# sch.net
KiCad netlist of a schematic drawn in EasyEDA
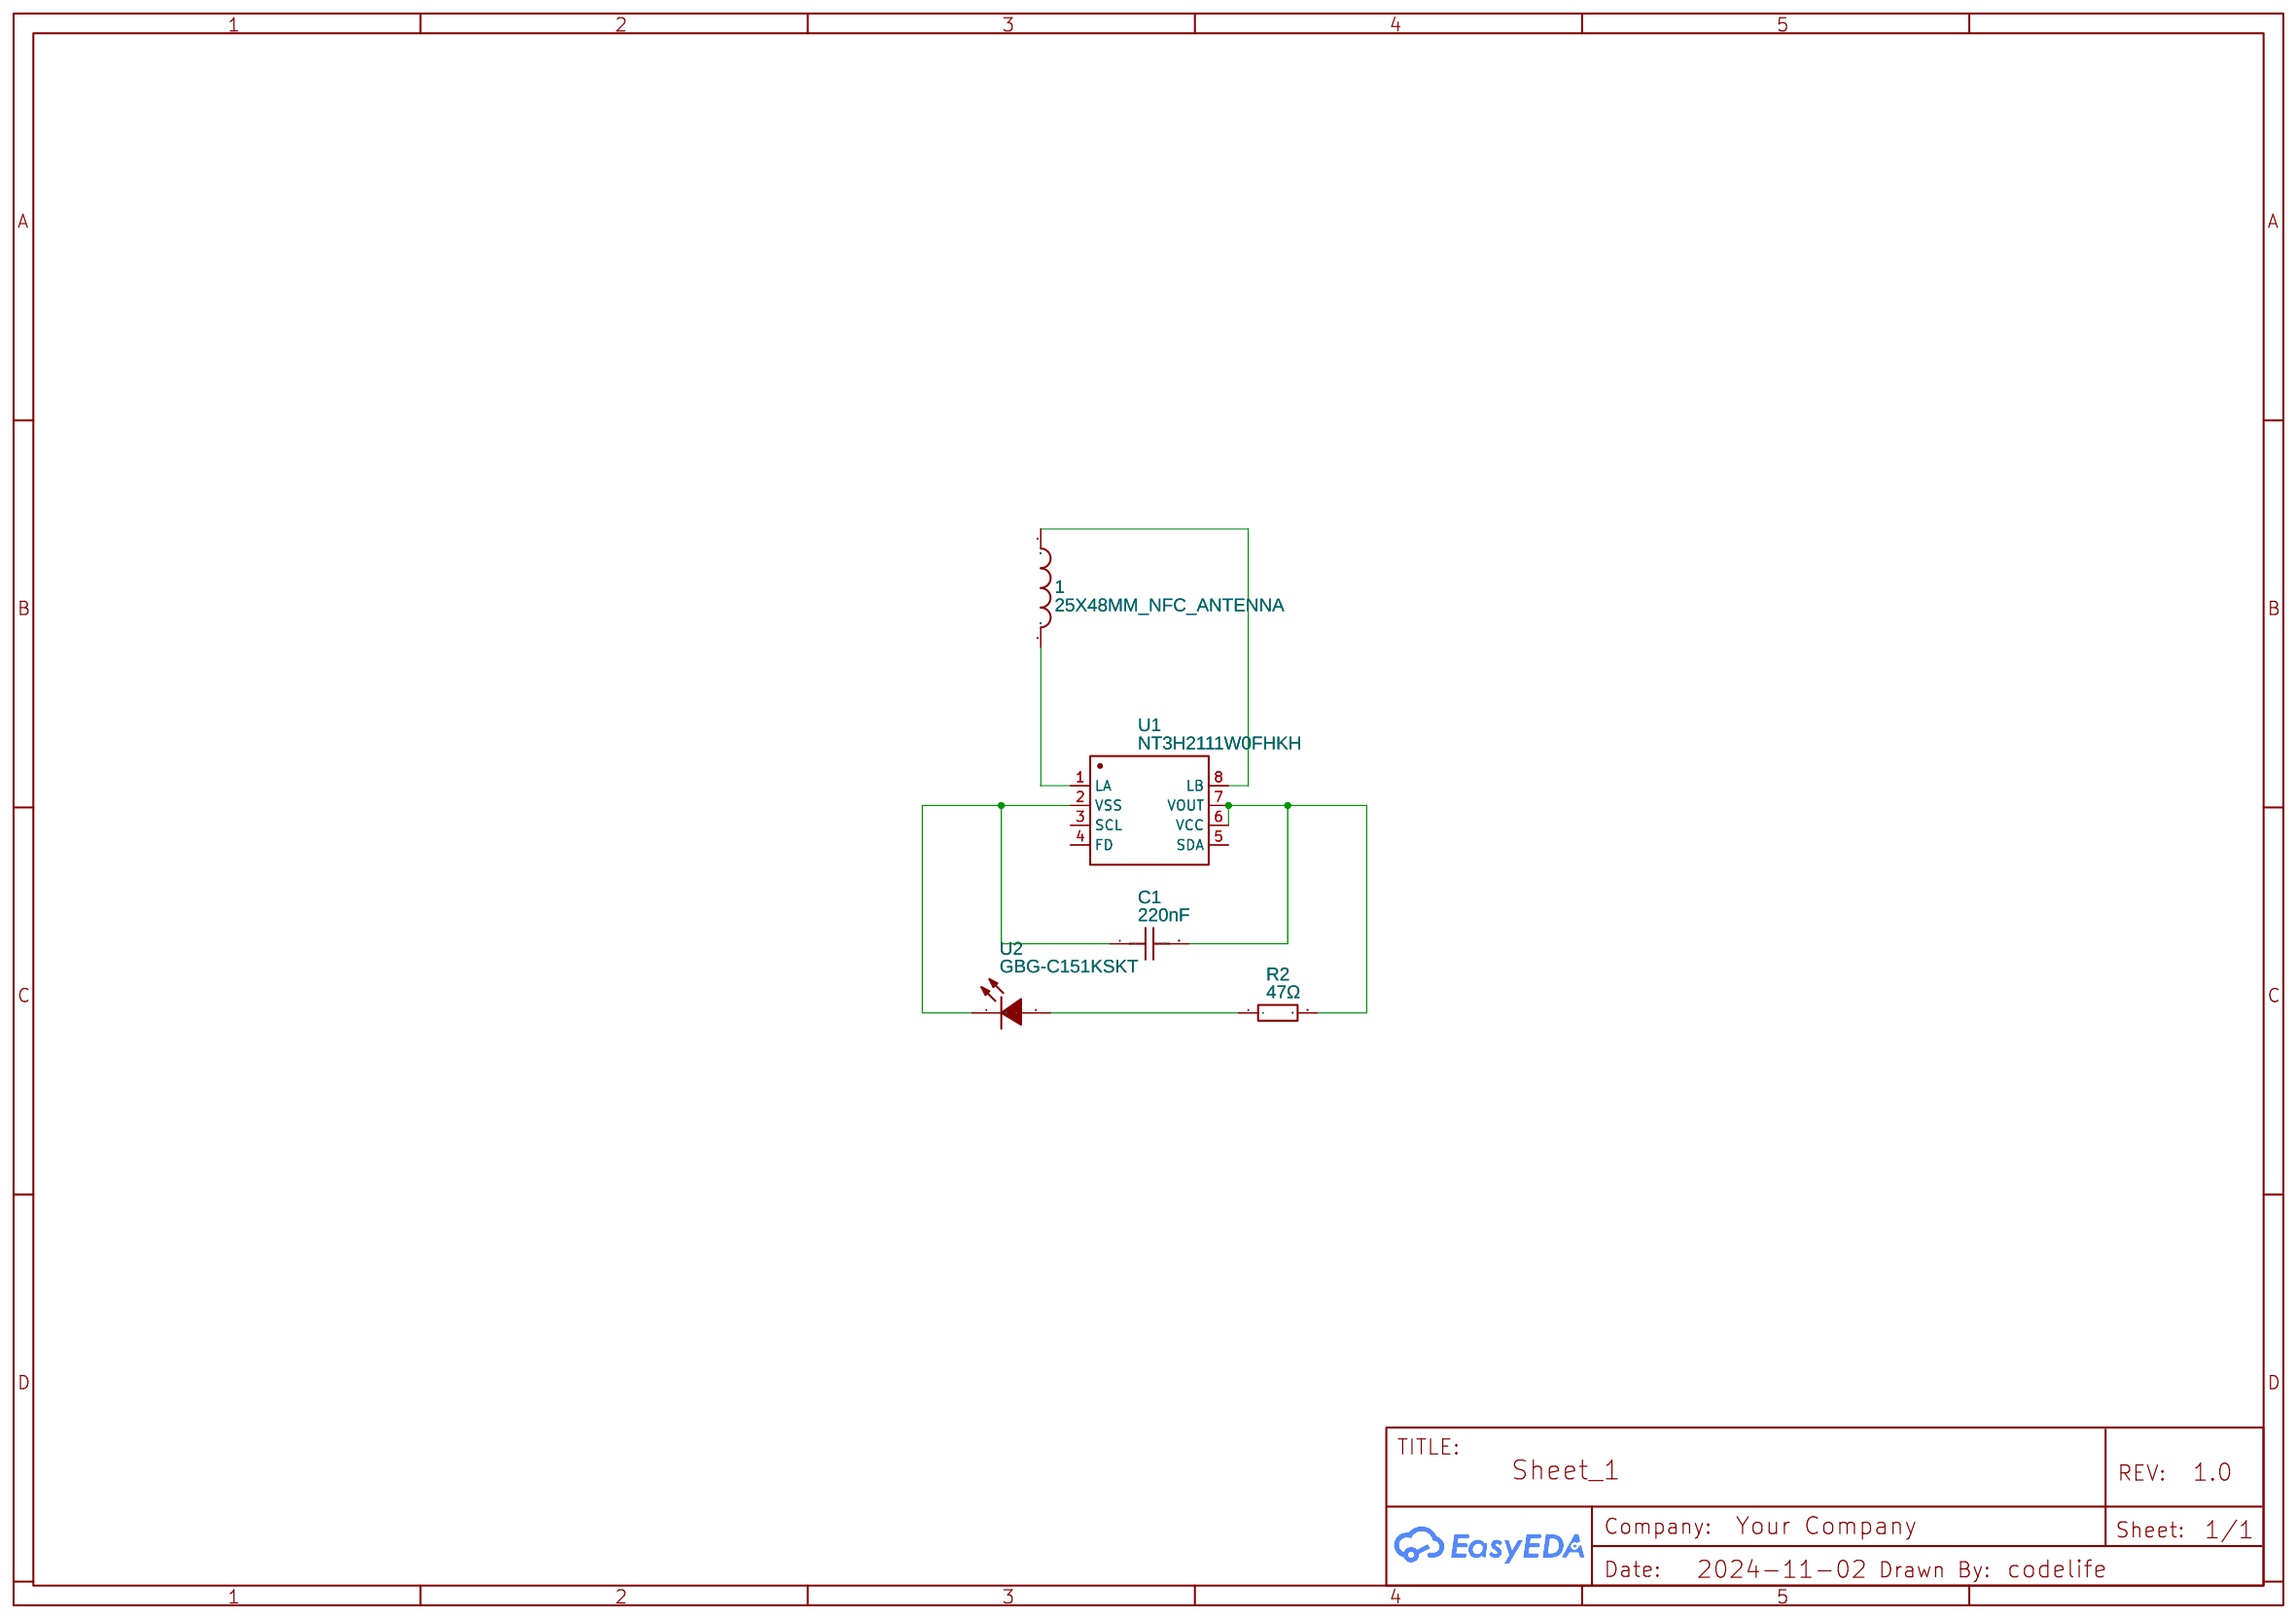
[diagram p0: schematic sheet]

(export (version "E")
  (design (tool "Eeschema 10.0.6"))
  (components
    (comp (ref "1") (value "25X48MM_NFC_ANTENNA") (libsource (lib "") (part "25X48MM_NFC_ANTENNA")))
    (comp (ref "C1")
      (value "220nF")
      (fields (field (name "Manufacturer Part") "0402X224K160NT") (field (name "Manufacturer") "FH(风华)"))
      (libsource (lib "") (part "0402X224K160NT"))
    )
    (comp (ref "R2")
      (value "47Ω")
      (fields
        (field (name "Manufacturer Part") "0402WGF470JTCE")
        (field (name "Manufacturer") "UNI-ROYAL(厚声)")
      )
      (libsource (lib "") (part "0402WGF470JTCE"))
    )
    (comp (ref "U1")
      (value "NT3H2111W0FHKH")
      (fields (field (name "Manufacturer") "NXP(恩智浦)"))
      (libsource (lib "") (part "NT3H2111W0FHKH"))
    )
    (comp (ref "U2")
      (value "GBG-C151KSKT")
      (fields (field (name "Manufacturer") "GBG"))
      (libsource (lib "") (part "GBG-C151KSKT"))
    )
  )
  (nets
    (net (code "1") (name "Net-(U1-LA)") (class "Default")
      (node (ref "1") (pin "P$2") (pinfunction "P$2_P$2") (pintype "bidirectional"))
      (node (ref "U1") (pin "1") (pinfunction "LA_1") (pintype "unspecified"))
    )
    (net (code "2") (name "Net-(U1-LB)") (class "Default")
      (node (ref "1") (pin "P$1") (pinfunction "P$1_P$1") (pintype "bidirectional"))
      (node (ref "U1") (pin "8") (pinfunction "LB_8") (pintype "unspecified"))
    )
    (net (code "3") (name "Net-(U1-VCC)") (class "Default")
      (node (ref "C1") (pin "2") (pinfunction "2_2") (pintype "unspecified"))
      (node (ref "R2") (pin "2") (pinfunction "2_2") (pintype "input"))
      (node (ref "U1") (pin "6") (pinfunction "VCC_6") (pintype "unspecified"))
      (node (ref "U1") (pin "7") (pinfunction "VOUT_7") (pintype "unspecified"))
    )
    (net (code "4") (name "Net-(U1-VSS)") (class "Default")
      (node (ref "C1") (pin "1") (pinfunction "1_1") (pintype "unspecified"))
      (node (ref "U1") (pin "2") (pinfunction "VSS_2") (pintype "unspecified"))
      (node (ref "U2") (pin "1") (pinfunction "C_1") (pintype "unspecified"))
    )
    (net (code "5") (name "Net-(U2-A)") (class "Default")
      (node (ref "R2") (pin "1") (pinfunction "1_1") (pintype "input"))
      (node (ref "U2") (pin "2") (pinfunction "A_2") (pintype "unspecified"))
    )
    (net (code "6") (name "unconnected-(U1-FD-Pad4)") (class "Default")
      (node (ref "U1") (pin "4") (pinfunction "FD_4") (pintype "unspecified"))
    )
    (net (code "7") (name "unconnected-(U1-SCL-Pad3)") (class "Default")
      (node (ref "U1") (pin "3") (pinfunction "SCL_3") (pintype "unspecified"))
    )
    (net (code "8") (name "unconnected-(U1-SDA-Pad5)") (class "Default")
      (node (ref "U1") (pin "5") (pinfunction "SDA_5") (pintype "unspecified"))
    )
  )
)
